# Xonik_Noise_A6.net
KiCad netlist of a schematic drawn in EAGLE
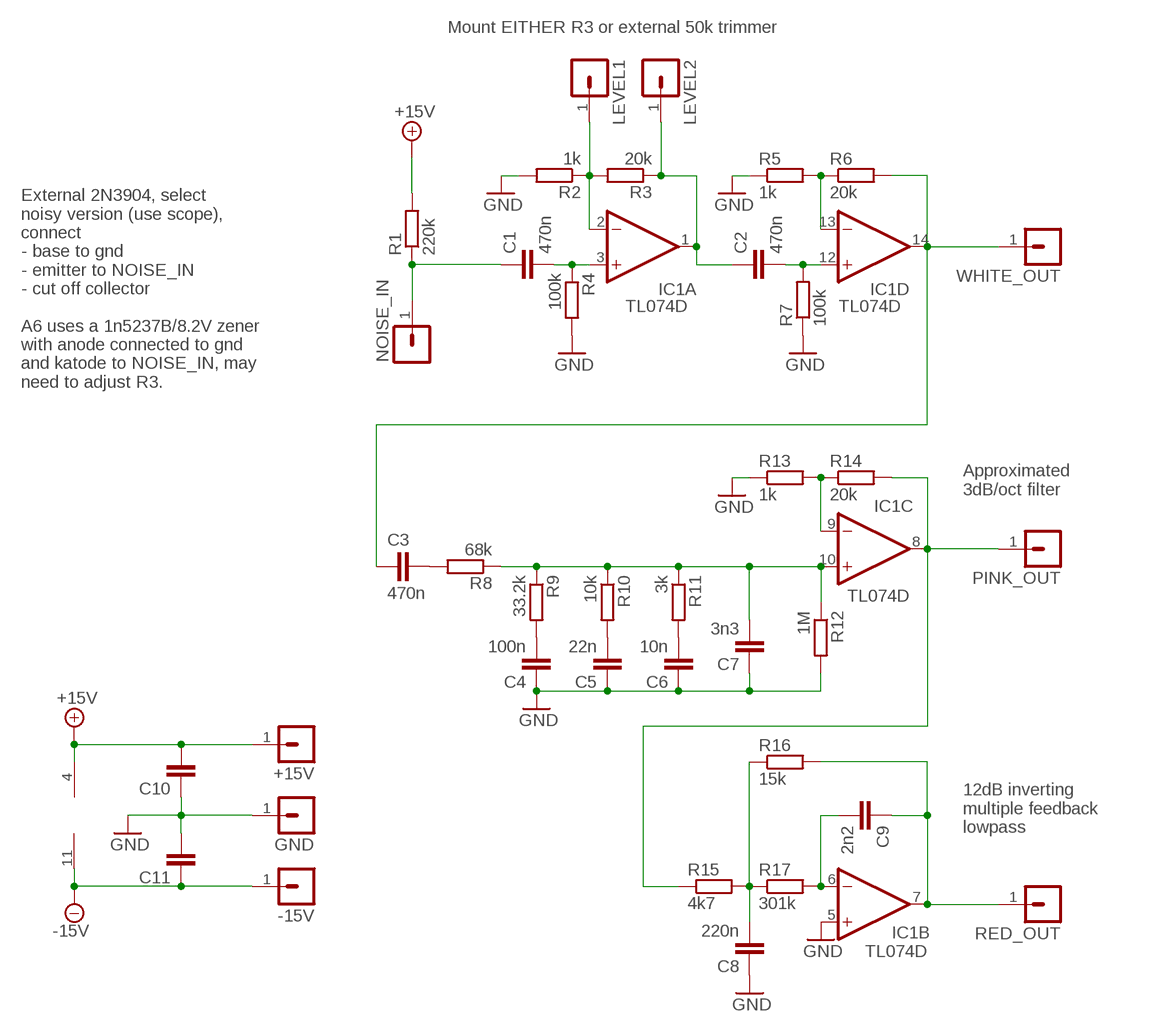
[diagram p0: schematic, sheet 1]

(export (version "E")
  (design (tool "Eeschema 10.0.6"))
  (components
    (comp (ref "+15V")
      (value "MA01-1JP")
      (footprint "eagle-import:SIP-PIN01-1J")
      (libsource (lib "eagle-import") (part "MA01-1JP"))
    )
    (comp (ref "-15V")
      (value "MA01-1JP")
      (footprint "eagle-import:SIP-PIN01-1J")
      (libsource (lib "eagle-import") (part "MA01-1JP"))
    )
    (comp (ref "C1")
      (value "470n")
      (footprint "eagle-import:C0805")
      (libsource (lib "eagle-import") (part "C-EUC0805"))
    )
    (comp (ref "C2")
      (value "470n")
      (footprint "eagle-import:C0805")
      (libsource (lib "eagle-import") (part "C-EUC0805"))
    )
    (comp (ref "C3")
      (value "470n")
      (footprint "eagle-import:C0805")
      (libsource (lib "eagle-import") (part "C-EUC0805"))
    )
    (comp (ref "C4")
      (value "100n")
      (footprint "eagle-import:C0805")
      (libsource (lib "eagle-import") (part "C-EUC0805"))
    )
    (comp (ref "C5")
      (value "22n")
      (footprint "eagle-import:C0805")
      (libsource (lib "eagle-import") (part "C-EUC0805"))
    )
    (comp (ref "C6")
      (value "10n")
      (footprint "eagle-import:C0805")
      (libsource (lib "eagle-import") (part "C-EUC0805"))
    )
    (comp (ref "C7")
      (value "3n3")
      (footprint "eagle-import:C0805")
      (libsource (lib "eagle-import") (part "C-EUC0805"))
    )
    (comp (ref "C8")
      (value "220n")
      (footprint "eagle-import:C0805")
      (libsource (lib "eagle-import") (part "C-EUC0805"))
    )
    (comp (ref "C9")
      (value "2n2")
      (footprint "eagle-import:C0805")
      (libsource (lib "eagle-import") (part "C-EUC0805"))
    )
    (comp (ref "C10")
      (value "C-EUC0603")
      (footprint "eagle-import:C0603")
      (libsource (lib "eagle-import") (part "C-EUC0603"))
    )
    (comp (ref "C11")
      (value "C-EUC0603")
      (footprint "eagle-import:C0603")
      (libsource (lib "eagle-import") (part "C-EUC0603"))
    )
    (comp (ref "GND")
      (value "MA01-1JP")
      (footprint "eagle-import:SIP-PIN01-1J")
      (libsource (lib "eagle-import") (part "MA01-1JP"))
    )
    (comp (ref "IC1")
      (value "TL074D")
      (footprint "eagle-import:SO14")
      (libsource (lib "eagle-import") (part "TL074D"))
    )
    (comp (ref "LEVEL1")
      (value "MA01-1JP")
      (footprint "eagle-import:SIP-PIN01-1J")
      (libsource (lib "eagle-import") (part "MA01-1JP"))
    )
    (comp (ref "LEVEL2")
      (value "MA01-1JP")
      (footprint "eagle-import:SIP-PIN01-1J")
      (libsource (lib "eagle-import") (part "MA01-1JP"))
    )
    (comp (ref "NOISE_IN")
      (value "MA01-1JP")
      (footprint "eagle-import:SIP-PIN01-1J")
      (libsource (lib "eagle-import") (part "MA01-1JP"))
    )
    (comp (ref "PINK_OUT")
      (value "MA01-1JP")
      (footprint "eagle-import:SIP-PIN01-1J")
      (libsource (lib "eagle-import") (part "MA01-1JP"))
    )
    (comp (ref "R1")
      (value "220k")
      (footprint "eagle-import:R0805")
      (libsource (lib "eagle-import") (part "R-EU_R0805"))
    )
    (comp (ref "R2")
      (value "1k")
      (footprint "eagle-import:R0805")
      (libsource (lib "eagle-import") (part "R-EU_R0805"))
    )
    (comp (ref "R3")
      (value "20k")
      (footprint "eagle-import:R0805")
      (libsource (lib "eagle-import") (part "R-EU_R0805"))
    )
    (comp (ref "R4")
      (value "100k")
      (footprint "eagle-import:R0805")
      (libsource (lib "eagle-import") (part "R-EU_R0805"))
    )
    (comp (ref "R5")
      (value "1k")
      (footprint "eagle-import:R0805")
      (libsource (lib "eagle-import") (part "R-EU_R0805"))
    )
    (comp (ref "R6")
      (value "20k")
      (footprint "eagle-import:R0805")
      (libsource (lib "eagle-import") (part "R-EU_R0805"))
    )
    (comp (ref "R7")
      (value "100k")
      (footprint "eagle-import:R0805")
      (libsource (lib "eagle-import") (part "R-EU_R0805"))
    )
    (comp (ref "R8")
      (value "68k")
      (footprint "eagle-import:R0805")
      (libsource (lib "eagle-import") (part "R-EU_R0805"))
    )
    (comp (ref "R9")
      (value "33.2k")
      (footprint "eagle-import:R0805")
      (libsource (lib "eagle-import") (part "R-EU_R0805"))
    )
    (comp (ref "R10")
      (value "10k")
      (footprint "eagle-import:R0805")
      (libsource (lib "eagle-import") (part "R-EU_R0805"))
    )
    (comp (ref "R11")
      (value "3k")
      (footprint "eagle-import:R0805")
      (libsource (lib "eagle-import") (part "R-EU_R0805"))
    )
    (comp (ref "R12")
      (value "1M")
      (footprint "eagle-import:R0805")
      (libsource (lib "eagle-import") (part "R-EU_R0805"))
    )
    (comp (ref "R13")
      (value "1k")
      (footprint "eagle-import:R0805")
      (libsource (lib "eagle-import") (part "R-EU_R0805"))
    )
    (comp (ref "R14")
      (value "20k")
      (footprint "eagle-import:R0805")
      (libsource (lib "eagle-import") (part "R-EU_R0805"))
    )
    (comp (ref "R15")
      (value "4k7")
      (footprint "eagle-import:R0805")
      (libsource (lib "eagle-import") (part "R-EU_R0805"))
    )
    (comp (ref "R16")
      (value "15k")
      (footprint "eagle-import:R0805")
      (libsource (lib "eagle-import") (part "R-EU_R0805"))
    )
    (comp (ref "R17")
      (value "301k")
      (footprint "eagle-import:R0805")
      (libsource (lib "eagle-import") (part "R-EU_R0805"))
    )
    (comp (ref "RED_OUT")
      (value "MA01-1JP")
      (footprint "eagle-import:SIP-PIN01-1J")
      (libsource (lib "eagle-import") (part "MA01-1JP"))
    )
    (comp (ref "WHITE_OUT")
      (value "MA01-1JP")
      (footprint "eagle-import:SIP-PIN01-1J")
      (libsource (lib "eagle-import") (part "MA01-1JP"))
    )
  )
  (nets
    (net (code "1") (name "+15V") (class "Default")
      (node (ref "+15V") (pin "1") (pinfunction "1_1") (pintype "passive"))
      (node (ref "C10") (pin "2") (pinfunction "2_2") (pintype "passive"))
      (node (ref "IC1") (pin "4") (pinfunction "V+_4") (pintype "power_in"))
      (node (ref "R1") (pin "2") (pinfunction "2_2") (pintype "passive"))
    )
    (net (code "2") (name "-15V") (class "Default")
      (node (ref "-15V") (pin "1") (pinfunction "1_1") (pintype "passive"))
      (node (ref "C11") (pin "1") (pinfunction "1_1") (pintype "passive"))
      (node (ref "IC1") (pin "11") (pinfunction "V-_11") (pintype "power_in"))
    )
    (net (code "3") (name "GND") (class "Default")
      (node (ref "C10") (pin "1") (pinfunction "1_1") (pintype "passive"))
      (node (ref "C11") (pin "2") (pinfunction "2_2") (pintype "passive"))
      (node (ref "C4") (pin "1") (pinfunction "1_1") (pintype "passive"))
      (node (ref "C5") (pin "1") (pinfunction "1_1") (pintype "passive"))
      (node (ref "C6") (pin "1") (pinfunction "1_1") (pintype "passive"))
      (node (ref "C7") (pin "1") (pinfunction "1_1") (pintype "passive"))
      (node (ref "C8") (pin "1") (pinfunction "1_1") (pintype "passive"))
      (node (ref "GND") (pin "1") (pinfunction "1_1") (pintype "passive"))
      (node (ref "IC1") (pin "5") (pinfunction "+IN_5") (pintype "input"))
      (node (ref "R12") (pin "2") (pinfunction "2_2") (pintype "passive"))
      (node (ref "R13") (pin "1") (pinfunction "1_1") (pintype "passive"))
      (node (ref "R2") (pin "2") (pinfunction "2_2") (pintype "passive"))
      (node (ref "R4") (pin "2") (pinfunction "2_2") (pintype "passive"))
      (node (ref "R5") (pin "1") (pinfunction "1_1") (pintype "passive"))
      (node (ref "R7") (pin "1") (pinfunction "1_1") (pintype "passive"))
    )
    (net (code "4") (name "Net-(C1-Pad1)") (class "Default")
      (node (ref "C1") (pin "1") (pinfunction "1_1") (pintype "passive"))
      (node (ref "NOISE_IN") (pin "1") (pinfunction "1_1") (pintype "passive"))
      (node (ref "R1") (pin "1") (pinfunction "1_1") (pintype "passive"))
    )
    (net (code "5") (name "Net-(C3-Pad2)") (class "Default")
      (node (ref "C3") (pin "2") (pinfunction "2_2") (pintype "passive"))
      (node (ref "R8") (pin "2") (pinfunction "2_2") (pintype "passive"))
    )
    (net (code "6") (name "Net-(C4-Pad2)") (class "Default")
      (node (ref "C4") (pin "2") (pinfunction "2_2") (pintype "passive"))
      (node (ref "R9") (pin "2") (pinfunction "2_2") (pintype "passive"))
    )
    (net (code "7") (name "Net-(C5-Pad2)") (class "Default")
      (node (ref "C5") (pin "2") (pinfunction "2_2") (pintype "passive"))
      (node (ref "R10") (pin "2") (pinfunction "2_2") (pintype "passive"))
    )
    (net (code "8") (name "Net-(C6-Pad2)") (class "Default")
      (node (ref "C6") (pin "2") (pinfunction "2_2") (pintype "passive"))
      (node (ref "R11") (pin "2") (pinfunction "2_2") (pintype "passive"))
    )
    (net (code "9") (name "Net-(C8-Pad2)") (class "Default")
      (node (ref "C8") (pin "2") (pinfunction "2_2") (pintype "passive"))
      (node (ref "R15") (pin "2") (pinfunction "2_2") (pintype "passive"))
      (node (ref "R16") (pin "1") (pinfunction "1_1") (pintype "passive"))
      (node (ref "R17") (pin "1") (pinfunction "1_1") (pintype "passive"))
    )
    (net (code "10") (name "Net-(IC1A-+IN)") (class "Default")
      (node (ref "C1") (pin "2") (pinfunction "2_2") (pintype "passive"))
      (node (ref "IC1") (pin "3") (pinfunction "+IN_3") (pintype "input"))
      (node (ref "R4") (pin "1") (pinfunction "1_1") (pintype "passive"))
    )
    (net (code "11") (name "Net-(IC1A--IN)") (class "Default")
      (node (ref "IC1") (pin "2") (pinfunction "-IN_2") (pintype "input"))
      (node (ref "LEVEL1") (pin "1") (pinfunction "1_1") (pintype "passive"))
      (node (ref "R2") (pin "1") (pinfunction "1_1") (pintype "passive"))
      (node (ref "R3") (pin "2") (pinfunction "2_2") (pintype "passive"))
    )
    (net (code "12") (name "Net-(IC1A-OUT)") (class "Default")
      (node (ref "C2") (pin "1") (pinfunction "1_1") (pintype "passive"))
      (node (ref "IC1") (pin "1") (pinfunction "OUT_1") (pintype "output"))
      (node (ref "LEVEL2") (pin "1") (pinfunction "1_1") (pintype "passive"))
      (node (ref "R3") (pin "1") (pinfunction "1_1") (pintype "passive"))
    )
    (net (code "13") (name "Net-(IC1B--IN)") (class "Default")
      (node (ref "C9") (pin "2") (pinfunction "2_2") (pintype "passive"))
      (node (ref "IC1") (pin "6") (pinfunction "-IN_6") (pintype "input"))
      (node (ref "R17") (pin "2") (pinfunction "2_2") (pintype "passive"))
    )
    (net (code "14") (name "Net-(IC1B-OUT)") (class "Default")
      (node (ref "C9") (pin "1") (pinfunction "1_1") (pintype "passive"))
      (node (ref "IC1") (pin "7") (pinfunction "OUT_7") (pintype "output"))
      (node (ref "R16") (pin "2") (pinfunction "2_2") (pintype "passive"))
      (node (ref "RED_OUT") (pin "1") (pinfunction "1_1") (pintype "passive"))
    )
    (net (code "15") (name "Net-(IC1C-+IN)") (class "Default")
      (node (ref "C7") (pin "2") (pinfunction "2_2") (pintype "passive"))
      (node (ref "IC1") (pin "10") (pinfunction "+IN_10") (pintype "input"))
      (node (ref "R10") (pin "1") (pinfunction "1_1") (pintype "passive"))
      (node (ref "R11") (pin "1") (pinfunction "1_1") (pintype "passive"))
      (node (ref "R12") (pin "1") (pinfunction "1_1") (pintype "passive"))
      (node (ref "R8") (pin "1") (pinfunction "1_1") (pintype "passive"))
      (node (ref "R9") (pin "1") (pinfunction "1_1") (pintype "passive"))
    )
    (net (code "16") (name "Net-(IC1C--IN)") (class "Default")
      (node (ref "IC1") (pin "9") (pinfunction "-IN_9") (pintype "input"))
      (node (ref "R13") (pin "2") (pinfunction "2_2") (pintype "passive"))
      (node (ref "R14") (pin "1") (pinfunction "1_1") (pintype "passive"))
    )
    (net (code "17") (name "Net-(IC1C-OUT)") (class "Default")
      (node (ref "IC1") (pin "8") (pinfunction "OUT_8") (pintype "output"))
      (node (ref "PINK_OUT") (pin "1") (pinfunction "1_1") (pintype "passive"))
      (node (ref "R14") (pin "2") (pinfunction "2_2") (pintype "passive"))
      (node (ref "R15") (pin "1") (pinfunction "1_1") (pintype "passive"))
    )
    (net (code "18") (name "Net-(IC1D-+IN)") (class "Default")
      (node (ref "C2") (pin "2") (pinfunction "2_2") (pintype "passive"))
      (node (ref "IC1") (pin "12") (pinfunction "+IN_12") (pintype "input"))
      (node (ref "R7") (pin "2") (pinfunction "2_2") (pintype "passive"))
    )
    (net (code "19") (name "Net-(IC1D--IN)") (class "Default")
      (node (ref "IC1") (pin "13") (pinfunction "-IN_13") (pintype "input"))
      (node (ref "R5") (pin "2") (pinfunction "2_2") (pintype "passive"))
      (node (ref "R6") (pin "1") (pinfunction "1_1") (pintype "passive"))
    )
    (net (code "20") (name "Net-(IC1D-OUT)") (class "Default")
      (node (ref "C3") (pin "1") (pinfunction "1_1") (pintype "passive"))
      (node (ref "IC1") (pin "14") (pinfunction "OUT_14") (pintype "output"))
      (node (ref "R6") (pin "2") (pinfunction "2_2") (pintype "passive"))
      (node (ref "WHITE_OUT") (pin "1") (pinfunction "1_1") (pintype "passive"))
    )
  )
)
